# 64K_SRAM_Memory_Controller.net
KiCad netlist of a schematic drawn in EAGLE
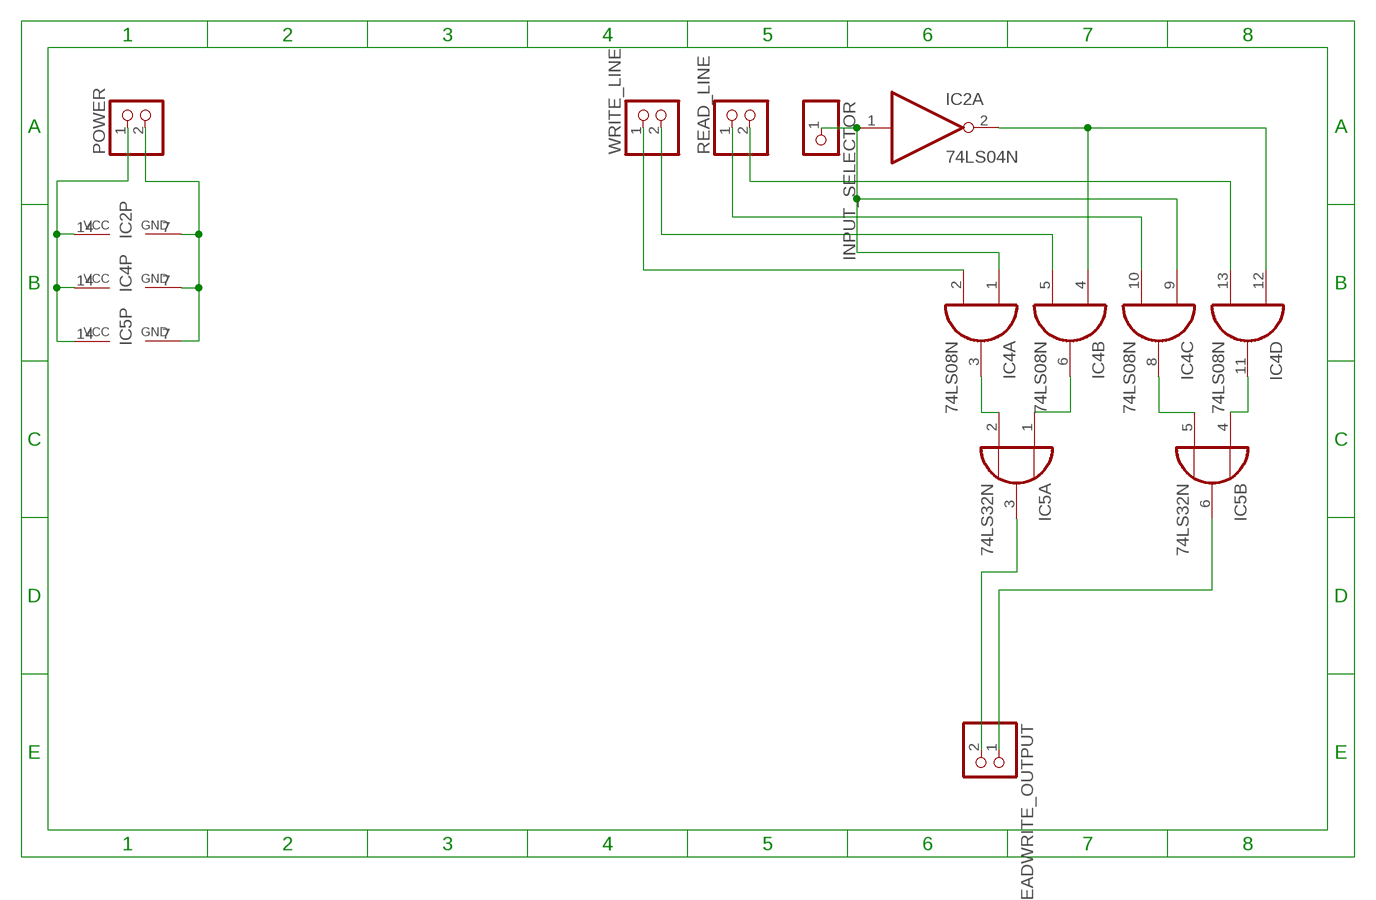
[diagram p0: schematic, sheet 1]

(export (version "E")
  (design (tool "Eeschema 10.0.6"))
  (components
    (comp (ref "IC2")
      (value "74LS04N")
      (footprint "eagle-import:DIL14")
      (libsource (lib "eagle-import") (part "7404NLS"))
    )
    (comp (ref "IC4")
      (value "74LS08N")
      (footprint "eagle-import:DIL14")
      (libsource (lib "eagle-import") (part "7408NLS"))
    )
    (comp (ref "IC5")
      (value "74LS32N")
      (footprint "eagle-import:DIL14")
      (libsource (lib "eagle-import") (part "7432NLS"))
    )
    (comp (ref "INPUT_SELECTOR")
      (value "PINHD-1X1")
      (footprint "eagle-import:1X01")
      (libsource (lib "eagle-import") (part "PINHD-1X1"))
    )
    (comp (ref "POWER")
      (value "PINHD-1X2")
      (footprint "eagle-import:1X02")
      (libsource (lib "eagle-import") (part "PINHD-1X2"))
    )
    (comp (ref "READWRITE_OUTPUT")
      (value "PINHD-1X2")
      (footprint "eagle-import:1X02")
      (libsource (lib "eagle-import") (part "PINHD-1X2"))
    )
    (comp (ref "READ_LINE")
      (value "PINHD-1X2")
      (footprint "eagle-import:1X02")
      (libsource (lib "eagle-import") (part "PINHD-1X2"))
    )
    (comp (ref "WRITE_LINE")
      (value "PINHD-1X2")
      (footprint "eagle-import:1X02")
      (libsource (lib "eagle-import") (part "PINHD-1X2"))
    )
  )
  (nets
    (net (code "1") (name "Net-(IC2A-I)") (class "Default")
      (node (ref "IC2") (pin "1") (pinfunction "I_1") (pintype "input"))
      (node (ref "IC4") (pin "1") (pinfunction "I0_1") (pintype "input"))
      (node (ref "IC4") (pin "9") (pinfunction "I0_9") (pintype "input"))
      (node (ref "INPUT_SELECTOR") (pin "1") (pinfunction "1_1") (pintype "passive"))
    )
    (net (code "2") (name "Net-(IC2A-O)") (class "Default")
      (node (ref "IC2") (pin "2") (pinfunction "O_2") (pintype "output"))
      (node (ref "IC4") (pin "12") (pinfunction "I0_12") (pintype "input"))
      (node (ref "IC4") (pin "4") (pinfunction "I0_4") (pintype "input"))
    )
    (net (code "3") (name "Net-(IC2G-GND)") (class "Default")
      (node (ref "IC2") (pin "7") (pinfunction "GND_7") (pintype "power_in"))
      (node (ref "IC4") (pin "7") (pinfunction "GND_7") (pintype "power_in"))
      (node (ref "IC5") (pin "7") (pinfunction "GND_7") (pintype "power_in"))
      (node (ref "POWER") (pin "2") (pinfunction "2_2") (pintype "passive"))
    )
    (net (code "4") (name "Net-(IC2G-VCC)") (class "Default")
      (node (ref "IC2") (pin "14") (pinfunction "VCC_14") (pintype "power_in"))
      (node (ref "IC4") (pin "14") (pinfunction "VCC_14") (pintype "power_in"))
      (node (ref "IC5") (pin "14") (pinfunction "VCC_14") (pintype "power_in"))
      (node (ref "POWER") (pin "1") (pinfunction "1_1") (pintype "passive"))
    )
    (net (code "5") (name "Net-(IC4A-I1)") (class "Default")
      (node (ref "IC4") (pin "2") (pinfunction "I1_2") (pintype "input"))
      (node (ref "WRITE_LINE") (pin "1") (pinfunction "1_1") (pintype "passive"))
    )
    (net (code "6") (name "Net-(IC4A-O)") (class "Default")
      (node (ref "IC4") (pin "3") (pinfunction "O_3") (pintype "output"))
      (node (ref "IC5") (pin "2") (pinfunction "I1_2") (pintype "input"))
    )
    (net (code "7") (name "Net-(IC4B-I1)") (class "Default")
      (node (ref "IC4") (pin "5") (pinfunction "I1_5") (pintype "input"))
      (node (ref "WRITE_LINE") (pin "2") (pinfunction "2_2") (pintype "passive"))
    )
    (net (code "8") (name "Net-(IC4B-O)") (class "Default")
      (node (ref "IC4") (pin "6") (pinfunction "O_6") (pintype "output"))
      (node (ref "IC5") (pin "1") (pinfunction "I0_1") (pintype "input"))
    )
    (net (code "9") (name "Net-(IC4C-I1)") (class "Default")
      (node (ref "IC4") (pin "10") (pinfunction "I1_10") (pintype "input"))
      (node (ref "READ_LINE") (pin "1") (pinfunction "1_1") (pintype "passive"))
    )
    (net (code "10") (name "Net-(IC4C-O)") (class "Default")
      (node (ref "IC4") (pin "8") (pinfunction "O_8") (pintype "output"))
      (node (ref "IC5") (pin "5") (pinfunction "I1_5") (pintype "input"))
    )
    (net (code "11") (name "Net-(IC4D-I1)") (class "Default")
      (node (ref "IC4") (pin "13") (pinfunction "I1_13") (pintype "input"))
      (node (ref "READ_LINE") (pin "2") (pinfunction "2_2") (pintype "passive"))
    )
    (net (code "12") (name "Net-(IC4D-O)") (class "Default")
      (node (ref "IC4") (pin "11") (pinfunction "O_11") (pintype "output"))
      (node (ref "IC5") (pin "4") (pinfunction "I0_4") (pintype "input"))
    )
    (net (code "13") (name "Net-(IC5A-O)") (class "Default")
      (node (ref "IC5") (pin "3") (pinfunction "O_3") (pintype "output"))
      (node (ref "READWRITE_OUTPUT") (pin "2") (pinfunction "2_2") (pintype "passive"))
    )
    (net (code "14") (name "Net-(IC5B-O)") (class "Default")
      (node (ref "IC5") (pin "6") (pinfunction "O_6") (pintype "output"))
      (node (ref "READWRITE_OUTPUT") (pin "1") (pinfunction "1_1") (pintype "passive"))
    )
  )
)
